# simpleUSBamp.net
KiCad netlist of a schematic drawn in EAGLE
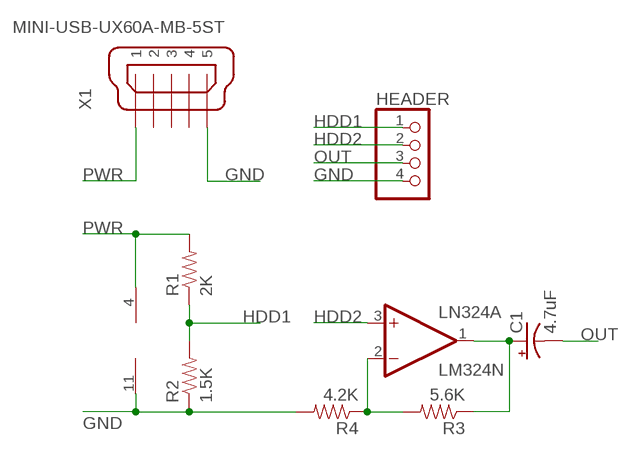
[diagram p0: schematic, sheet 1]

(export (version "E")
  (design (tool "Eeschema 10.0.6"))
  (components
    (comp (ref "C1")
      (value "4.7uF")
      (footprint "eagle-import:CPOL-RADIAL-100UF-25V")
      (libsource (lib "eagle-import") (part "CAP_POLPTH1"))
    )
    (comp (ref "HEADER")
      (value "PINHD-1X4")
      (footprint "eagle-import:1X04")
      (libsource (lib "eagle-import") (part "PINHD-1X4"))
    )
    (comp (ref "LN324")
      (value "LM324N")
      (footprint "eagle-import:DIL14")
      (libsource (lib "eagle-import") (part "LM324N"))
    )
    (comp (ref "R1")
      (value "2K")
      (footprint "eagle-import:AXIAL-0.4")
      (libsource (lib "eagle-import") (part "RESISTORPTH-1/4W"))
    )
    (comp (ref "R2")
      (value "1.5K")
      (footprint "eagle-import:AXIAL-0.4")
      (libsource (lib "eagle-import") (part "RESISTORPTH-1/4W"))
    )
    (comp (ref "R3")
      (value "5.6K")
      (footprint "eagle-import:AXIAL-0.4")
      (libsource (lib "eagle-import") (part "RESISTORPTH-1/4W"))
    )
    (comp (ref "R4")
      (value "4.2K")
      (footprint "eagle-import:AXIAL-0.4")
      (libsource (lib "eagle-import") (part "RESISTORPTH-1/4W"))
    )
    (comp (ref "X1")
      (value "MINI-USB-UX60A-MB-5ST")
      (footprint "eagle-import:UX60A-MB-5ST")
      (libsource (lib "eagle-import") (part "MINI-USB-UX60A-MB-5ST"))
    )
  )
  (nets
    (net (code "1") (name "/GND") (class "Default")
      (node (ref "HEADER") (pin "4") (pinfunction "4_4") (pintype "passive"))
      (node (ref "LN324") (pin "11") (pinfunction "V-_11") (pintype "power_in"))
      (node (ref "R2") (pin "P$1") (pinfunction "1_P$1") (pintype "passive"))
      (node (ref "R4") (pin "P$2") (pinfunction "2_P$2") (pintype "passive"))
      (node (ref "X1") (pin "5") (pinfunction "5_5") (pintype "input"))
    )
    (net (code "2") (name "/HDD1") (class "Default")
      (node (ref "HEADER") (pin "1") (pinfunction "1_1") (pintype "passive"))
      (node (ref "R1") (pin "P$1") (pinfunction "1_P$1") (pintype "passive"))
      (node (ref "R2") (pin "P$2") (pinfunction "2_P$2") (pintype "passive"))
    )
    (net (code "3") (name "/HDD2") (class "Default")
      (node (ref "HEADER") (pin "2") (pinfunction "2_2") (pintype "passive"))
      (node (ref "LN324") (pin "3") (pinfunction "+IN_3") (pintype "input"))
    )
    (net (code "4") (name "/OUT") (class "Default")
      (node (ref "C1") (pin "2") (pinfunction "-_2") (pintype "passive"))
      (node (ref "HEADER") (pin "3") (pinfunction "3_3") (pintype "passive"))
    )
    (net (code "5") (name "/PWR") (class "Default")
      (node (ref "LN324") (pin "4") (pinfunction "V+_4") (pintype "power_in"))
      (node (ref "R1") (pin "P$2") (pinfunction "2_P$2") (pintype "passive"))
      (node (ref "X1") (pin "1") (pinfunction "1_1") (pintype "input"))
    )
    (net (code "6") (name "Net-(C1-+)") (class "Default")
      (node (ref "C1") (pin "1") (pinfunction "+_1") (pintype "passive"))
      (node (ref "LN324") (pin "1") (pinfunction "OUT_1") (pintype "output"))
      (node (ref "R3") (pin "P$1") (pinfunction "1_P$1") (pintype "passive"))
    )
    (net (code "7") (name "Net-(LN324A--IN)") (class "Default")
      (node (ref "LN324") (pin "2") (pinfunction "-IN_2") (pintype "input"))
      (node (ref "R3") (pin "P$2") (pinfunction "2_P$2") (pintype "passive"))
      (node (ref "R4") (pin "P$1") (pinfunction "1_P$1") (pintype "passive"))
    )
    (net (code "8") (name "unconnected-(X1-Pad2)") (class "Default")
      (node (ref "X1") (pin "2") (pinfunction "2_2") (pintype "input"))
    )
    (net (code "9") (name "unconnected-(X1-Pad3)") (class "Default")
      (node (ref "X1") (pin "3") (pinfunction "3_3") (pintype "input"))
    )
    (net (code "10") (name "unconnected-(X1-Pad4)") (class "Default")
      (node (ref "X1") (pin "4") (pinfunction "4_4") (pintype "input"))
    )
  )
)
